# 1_uC.net
KiCad netlist of a schematic drawn in Altium Designer
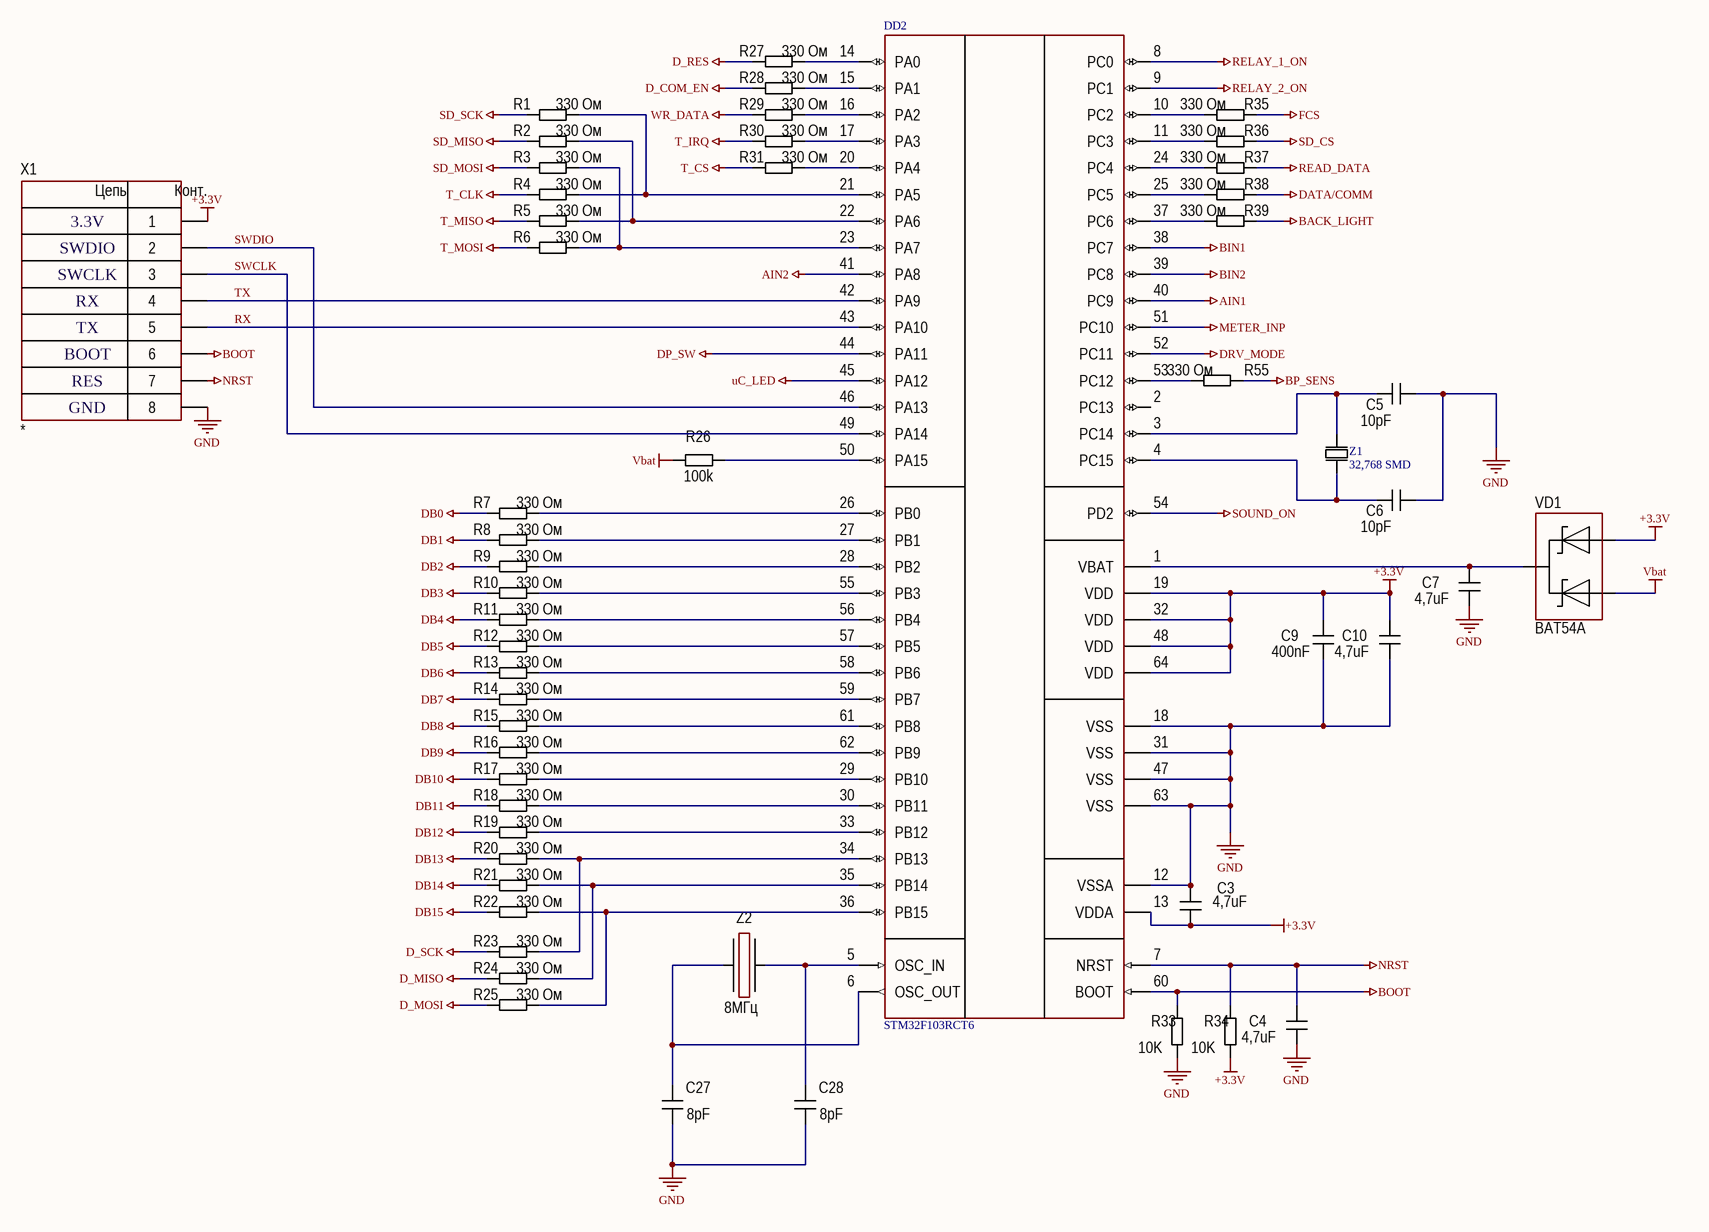
[diagram p0: 1_uC.SchDoc]

(export (version "E")
  (design (tool "Eeschema 10.0.6"))
  (components
    (comp (ref "C3")
      (value "4,7uF")
      (footprint "CH0402C")
      (description "0402")
      (libsource (lib "Condensators") (part "Capacitor"))
    )
    (comp (ref "C4")
      (value "4,7uF")
      (footprint "CH0402C")
      (description "0402")
      (libsource (lib "Condensators") (part "Capacitor"))
    )
    (comp (ref "C5")
      (value "10pF")
      (footprint "CH0402C")
      (description "0402")
      (libsource (lib "Condensators") (part "Capacitor"))
    )
    (comp (ref "C6")
      (value "10pF")
      (footprint "CH0402C")
      (description "0402")
      (libsource (lib "Condensators") (part "Capacitor"))
    )
    (comp (ref "C7")
      (value "4,7uF")
      (footprint "CH0402C")
      (libsource (lib "Condensators") (part "Capacitor"))
    )
    (comp (ref "C9")
      (value "400nF")
      (footprint "CH0402C")
      (description "0402")
      (libsource (lib "Condensators") (part "Capacitor"))
    )
    (comp (ref "C10")
      (value "4,7uF")
      (footprint "CH0402C")
      (description "0402")
      (libsource (lib "Condensators") (part "Capacitor"))
    )
    (comp (ref "C27")
      (value "8pF")
      (footprint "CH0402C")
      (description "0402")
      (libsource (lib "Condensators") (part "Capacitor"))
    )
    (comp (ref "C28")
      (value "8pF")
      (footprint "CH0402C")
      (description "0402")
      (libsource (lib "Condensators") (part "Capacitor"))
    )
    (comp (ref "DD2")
      (value "STM32F103RCT6")
      (footprint "64-LQFP")
      (description "Cortex-M3 (64-LQFP)")
      (libsource (lib "MicroIC") (part "STM32F103RCT6"))
    )
    (comp (ref "R1")
      (value "330 Ом")
      (footprint "CH0603R")
      (description "0603")
      (libsource (lib "Resistors") (part "Resistor"))
    )
    (comp (ref "R2")
      (value "330 Ом")
      (footprint "CH0603R")
      (description "0603")
      (libsource (lib "Resistors") (part "Resistor"))
    )
    (comp (ref "R3")
      (value "330 Ом")
      (footprint "CH0603R")
      (description "0603")
      (libsource (lib "Resistors") (part "Resistor"))
    )
    (comp (ref "R4")
      (value "330 Ом")
      (footprint "CH0603R")
      (description "0603")
      (libsource (lib "Resistors") (part "Resistor"))
    )
    (comp (ref "R5")
      (value "330 Ом")
      (footprint "CH0603R")
      (description "0603")
      (libsource (lib "Resistors") (part "Resistor"))
    )
    (comp (ref "R6")
      (value "330 Ом")
      (footprint "CH0603R")
      (description "0603")
      (libsource (lib "Resistors") (part "Resistor"))
    )
    (comp (ref "R7")
      (value "330 Ом")
      (footprint "CH0603R")
      (description "0603")
      (libsource (lib "Resistors") (part "Resistor"))
    )
    (comp (ref "R8")
      (value "330 Ом")
      (footprint "CH0603R")
      (description "0603")
      (libsource (lib "Resistors") (part "Resistor"))
    )
    (comp (ref "R9")
      (value "330 Ом")
      (footprint "CH0603R")
      (description "0603")
      (libsource (lib "Resistors") (part "Resistor"))
    )
    (comp (ref "R10")
      (value "330 Ом")
      (footprint "CH0603R")
      (description "0603")
      (libsource (lib "Resistors") (part "Resistor"))
    )
    (comp (ref "R11")
      (value "330 Ом")
      (footprint "CH0603R")
      (description "0603")
      (libsource (lib "Resistors") (part "Resistor"))
    )
    (comp (ref "R12")
      (value "330 Ом")
      (footprint "CH0603R")
      (description "0603")
      (libsource (lib "Resistors") (part "Resistor"))
    )
    (comp (ref "R13")
      (value "330 Ом")
      (footprint "CH0603R")
      (description "0603")
      (libsource (lib "Resistors") (part "Resistor"))
    )
    (comp (ref "R14")
      (value "330 Ом")
      (footprint "CH0603R")
      (description "0603")
      (libsource (lib "Resistors") (part "Resistor"))
    )
    (comp (ref "R15")
      (value "330 Ом")
      (footprint "CH0603R")
      (description "0603")
      (libsource (lib "Resistors") (part "Resistor"))
    )
    (comp (ref "R16")
      (value "330 Ом")
      (footprint "CH0603R")
      (description "0603")
      (libsource (lib "Resistors") (part "Resistor"))
    )
    (comp (ref "R17")
      (value "330 Ом")
      (footprint "CH0603R")
      (description "0603")
      (libsource (lib "Resistors") (part "Resistor"))
    )
    (comp (ref "R18")
      (value "330 Ом")
      (footprint "CH0603R")
      (description "0603")
      (libsource (lib "Resistors") (part "Resistor"))
    )
    (comp (ref "R19")
      (value "330 Ом")
      (footprint "CH0603R")
      (description "0603")
      (libsource (lib "Resistors") (part "Resistor"))
    )
    (comp (ref "R20")
      (value "330 Ом")
      (footprint "CH0603R")
      (description "0603")
      (libsource (lib "Resistors") (part "Resistor"))
    )
    (comp (ref "R21")
      (value "330 Ом")
      (footprint "CH0603R")
      (description "0603")
      (libsource (lib "Resistors") (part "Resistor"))
    )
    (comp (ref "R22")
      (value "330 Ом")
      (footprint "CH0603R")
      (description "0603")
      (libsource (lib "Resistors") (part "Resistor"))
    )
    (comp (ref "R23")
      (value "330 Ом")
      (footprint "CH0603R")
      (description "0603")
      (libsource (lib "Resistors") (part "Resistor"))
    )
    (comp (ref "R24")
      (value "330 Ом")
      (footprint "CH0603R")
      (description "0603")
      (libsource (lib "Resistors") (part "Resistor"))
    )
    (comp (ref "R25")
      (value "330 Ом")
      (footprint "CH0603R")
      (description "0603")
      (libsource (lib "Resistors") (part "Resistor"))
    )
    (comp (ref "R26")
      (value "100k")
      (footprint "CH0603R")
      (description "0603")
      (libsource (lib "Resistors") (part "Resistor"))
    )
    (comp (ref "R27")
      (value "330 Ом")
      (footprint "CH0603R")
      (description "0603")
      (libsource (lib "Resistors") (part "Resistor"))
    )
    (comp (ref "R28")
      (value "330 Ом")
      (footprint "CH0603R")
      (description "0603")
      (libsource (lib "Resistors") (part "Resistor"))
    )
    (comp (ref "R29")
      (value "330 Ом")
      (footprint "CH0603R")
      (description "0603")
      (libsource (lib "Resistors") (part "Resistor"))
    )
    (comp (ref "R30")
      (value "330 Ом")
      (footprint "CH0603R")
      (description "0603")
      (libsource (lib "Resistors") (part "Resistor"))
    )
    (comp (ref "R31")
      (value "330 Ом")
      (footprint "CH0603R")
      (description "0603")
      (libsource (lib "Resistors") (part "Resistor"))
    )
    (comp (ref "R33")
      (value "10K")
      (footprint "CH0805R")
      (description "0805")
      (libsource (lib "Resistors") (part "Resistor"))
    )
    (comp (ref "R34")
      (value "10K")
      (footprint "CH0805R")
      (description "0805")
      (libsource (lib "Resistors") (part "Resistor"))
    )
    (comp (ref "R35")
      (value "330 Ом")
      (footprint "CH0603R")
      (description "0603")
      (libsource (lib "Resistors") (part "Resistor"))
    )
    (comp (ref "R36")
      (value "330 Ом")
      (footprint "CH0603R")
      (description "0603")
      (libsource (lib "Resistors") (part "Resistor"))
    )
    (comp (ref "R37")
      (value "330 Ом")
      (footprint "CH0603R")
      (description "0603")
      (libsource (lib "Resistors") (part "Resistor"))
    )
    (comp (ref "R38")
      (value "330 Ом")
      (footprint "CH0603R")
      (description "0603")
      (libsource (lib "Resistors") (part "Resistor"))
    )
    (comp (ref "R39")
      (value "330 Ом")
      (footprint "CH0603R")
      (description "0603")
      (libsource (lib "Resistors") (part "Resistor"))
    )
    (comp (ref "R55")
      (value "330 Ом")
      (footprint "CH0603R")
      (description "0603")
      (libsource (lib "Resistors") (part "Resistor"))
    )
    (comp (ref "VD1")
      (value "BAT54A")
      (footprint "SOT23_123")
      (description "SOT-23")
      (libsource (lib "Diods") (part "Diod Schottky Array v.1"))
    )
    (comp (ref "X1")
      (value "*")
      (footprint "CON: PLS-8")
      (description "Pin header 8")
      (libsource (lib "Connectors") (part "8-Connector"))
    )
    (comp (ref "Z1")
      (value "32,768 SMD")
      (footprint "SMD 32.768KHz")
      (description "32,768 kHz SMD 8mm x 3.8mm 12,5pF")
      (libsource (lib "Melochi") (part "Kvarc_32,768"))
    )
    (comp (ref "Z2")
      (value "8МГц")
      (footprint "OSC: ABM3")
      (description "NX5032GA-8MHz")
      (libsource (lib "Melochi") (part "Oscillator"))
    )
  )
  (nets
    (net (code "1") (name "+3.3V") (class "Default")
      (node (ref "C10") (pin "2") (pinfunction "2_2") (pintype "passive"))
      (node (ref "C3") (pin "1") (pinfunction "1_1") (pintype "passive"))
      (node (ref "C9") (pin "1") (pinfunction "1_1") (pintype "passive"))
      (node (ref "DD2") (pin "13") (pinfunction "VDDA_13") (pintype "power_in"))
      (node (ref "DD2") (pin "19") (pinfunction "VDD_19") (pintype "power_in"))
      (node (ref "DD2") (pin "32") (pinfunction "VDD_32") (pintype "power_in"))
      (node (ref "DD2") (pin "48") (pinfunction "VDD_48") (pintype "power_in"))
      (node (ref "DD2") (pin "64") (pinfunction "VDD_64") (pintype "power_in"))
      (node (ref "R34") (pin "1") (pinfunction "1_1") (pintype "passive"))
      (node (ref "VD1") (pin "1") (pinfunction "1_1") (pintype "passive"))
      (node (ref "X1") (pin "1") (pinfunction "1_1") (pintype "passive"))
    )
    (net (code "2") (name "/RX") (class "Default")
      (node (ref "DD2") (pin "43") (pinfunction "PA10_43") (pintype "bidirectional"))
      (node (ref "X1") (pin "5") (pinfunction "5_5") (pintype "power_in"))
    )
    (net (code "3") (name "/SWCLK") (class "Default")
      (node (ref "DD2") (pin "49") (pinfunction "PA14_49") (pintype "bidirectional"))
      (node (ref "X1") (pin "3") (pinfunction "3_3") (pintype "power_in"))
    )
    (net (code "4") (name "/SWDIO") (class "Default")
      (node (ref "DD2") (pin "46") (pinfunction "PA13_46") (pintype "bidirectional"))
      (node (ref "X1") (pin "2") (pinfunction "2_2") (pintype "passive"))
    )
    (net (code "5") (name "/TX") (class "Default")
      (node (ref "DD2") (pin "42") (pinfunction "PA9_42") (pintype "bidirectional"))
      (node (ref "X1") (pin "4") (pinfunction "4_4") (pintype "power_in"))
    )
    (net (code "6") (name "AIN1") (class "Default")
      (node (ref "DD2") (pin "40") (pinfunction "PC9_40") (pintype "bidirectional"))
    )
    (net (code "7") (name "AIN2") (class "Default")
      (node (ref "DD2") (pin "41") (pinfunction "PA8_41") (pintype "bidirectional"))
    )
    (net (code "8") (name "BACK_LIGHT") (class "Default")
      (node (ref "R39") (pin "1") (pinfunction "1_1") (pintype "passive"))
    )
    (net (code "9") (name "BIN1") (class "Default")
      (node (ref "DD2") (pin "38") (pinfunction "PC7_38") (pintype "bidirectional"))
    )
    (net (code "10") (name "BIN2") (class "Default")
      (node (ref "DD2") (pin "39") (pinfunction "PC8_39") (pintype "bidirectional"))
    )
    (net (code "11") (name "BOOT") (class "Default")
      (node (ref "DD2") (pin "60") (pinfunction "BOOT_60") (pintype "input"))
      (node (ref "R33") (pin "2") (pinfunction "2_2") (pintype "passive"))
      (node (ref "X1") (pin "6") (pinfunction "6_6") (pintype "power_in"))
    )
    (net (code "12") (name "BP_SENS") (class "Default")
      (node (ref "R55") (pin "1") (pinfunction "1_1") (pintype "passive"))
    )
    (net (code "13") (name "DATA{slash}COMM") (class "Default")
      (node (ref "R38") (pin "1") (pinfunction "1_1") (pintype "passive"))
    )
    (net (code "14") (name "DB0") (class "Default")
      (node (ref "R7") (pin "1") (pinfunction "1_1") (pintype "passive"))
    )
    (net (code "15") (name "DB1") (class "Default")
      (node (ref "R8") (pin "1") (pinfunction "1_1") (pintype "passive"))
    )
    (net (code "16") (name "DB2") (class "Default")
      (node (ref "R9") (pin "1") (pinfunction "1_1") (pintype "passive"))
    )
    (net (code "17") (name "DB3") (class "Default")
      (node (ref "R10") (pin "1") (pinfunction "1_1") (pintype "passive"))
    )
    (net (code "18") (name "DB4") (class "Default")
      (node (ref "R11") (pin "1") (pinfunction "1_1") (pintype "passive"))
    )
    (net (code "19") (name "DB5") (class "Default")
      (node (ref "R12") (pin "1") (pinfunction "1_1") (pintype "passive"))
    )
    (net (code "20") (name "DB6") (class "Default")
      (node (ref "R13") (pin "1") (pinfunction "1_1") (pintype "passive"))
    )
    (net (code "21") (name "DB7") (class "Default")
      (node (ref "R14") (pin "1") (pinfunction "1_1") (pintype "passive"))
    )
    (net (code "22") (name "DB8") (class "Default")
      (node (ref "R15") (pin "1") (pinfunction "1_1") (pintype "passive"))
    )
    (net (code "23") (name "DB9") (class "Default")
      (node (ref "R16") (pin "1") (pinfunction "1_1") (pintype "passive"))
    )
    (net (code "24") (name "DB10") (class "Default")
      (node (ref "R17") (pin "1") (pinfunction "1_1") (pintype "passive"))
    )
    (net (code "25") (name "DB11") (class "Default")
      (node (ref "R18") (pin "1") (pinfunction "1_1") (pintype "passive"))
    )
    (net (code "26") (name "DB12") (class "Default")
      (node (ref "R19") (pin "1") (pinfunction "1_1") (pintype "passive"))
    )
    (net (code "27") (name "DB13") (class "Default")
      (node (ref "R20") (pin "1") (pinfunction "1_1") (pintype "passive"))
    )
    (net (code "28") (name "DB14") (class "Default")
      (node (ref "R21") (pin "1") (pinfunction "1_1") (pintype "passive"))
    )
    (net (code "29") (name "DB15") (class "Default")
      (node (ref "R22") (pin "1") (pinfunction "1_1") (pintype "passive"))
    )
    (net (code "30") (name "DP_SW") (class "Default")
      (node (ref "DD2") (pin "44") (pinfunction "PA11_44") (pintype "bidirectional"))
    )
    (net (code "31") (name "DRV_MODE") (class "Default")
      (node (ref "DD2") (pin "52") (pinfunction "PC11_52") (pintype "bidirectional"))
    )
    (net (code "32") (name "D_COM_EN") (class "Default")
      (node (ref "R28") (pin "1") (pinfunction "1_1") (pintype "passive"))
    )
    (net (code "33") (name "D_MISO") (class "Default")
      (node (ref "R24") (pin "1") (pinfunction "1_1") (pintype "passive"))
    )
    (net (code "34") (name "D_MOSI") (class "Default")
      (node (ref "R25") (pin "1") (pinfunction "1_1") (pintype "passive"))
    )
    (net (code "35") (name "D_RES") (class "Default")
      (node (ref "R27") (pin "1") (pinfunction "1_1") (pintype "passive"))
    )
    (net (code "36") (name "D_SCK") (class "Default")
      (node (ref "R23") (pin "1") (pinfunction "1_1") (pintype "passive"))
    )
    (net (code "37") (name "FCS") (class "Default")
      (node (ref "R35") (pin "1") (pinfunction "1_1") (pintype "passive"))
    )
    (net (code "38") (name "GND") (class "Default")
      (node (ref "C10") (pin "1") (pinfunction "1_1") (pintype "passive"))
      (node (ref "C27") (pin "1") (pinfunction "1_1") (pintype "passive"))
      (node (ref "C28") (pin "1") (pinfunction "1_1") (pintype "passive"))
      (node (ref "C3") (pin "2") (pinfunction "2_2") (pintype "passive"))
      (node (ref "C4") (pin "1") (pinfunction "1_1") (pintype "passive"))
      (node (ref "C5") (pin "2") (pinfunction "2_2") (pintype "passive"))
      (node (ref "C6") (pin "1") (pinfunction "1_1") (pintype "passive"))
      (node (ref "C7") (pin "1") (pinfunction "1_1") (pintype "passive"))
      (node (ref "C9") (pin "2") (pinfunction "2_2") (pintype "passive"))
      (node (ref "DD2") (pin "12") (pinfunction "VSSA_12") (pintype "power_in"))
      (node (ref "DD2") (pin "18") (pinfunction "VSS_18") (pintype "power_in"))
      (node (ref "DD2") (pin "31") (pinfunction "VSS_31") (pintype "power_in"))
      (node (ref "DD2") (pin "47") (pinfunction "VSS_47") (pintype "power_in"))
      (node (ref "DD2") (pin "63") (pinfunction "VSS_63") (pintype "power_in"))
      (node (ref "R33") (pin "1") (pinfunction "1_1") (pintype "passive"))
      (node (ref "X1") (pin "8") (pinfunction "8_8") (pintype "power_in"))
    )
    (net (code "39") (name "METER_INP") (class "Default")
      (node (ref "DD2") (pin "51") (pinfunction "PC10_51") (pintype "bidirectional"))
    )
    (net (code "40") (name "NRST") (class "Default")
      (node (ref "C4") (pin "2") (pinfunction "2_2") (pintype "passive"))
      (node (ref "DD2") (pin "7") (pinfunction "NRST_7") (pintype "input"))
      (node (ref "R34") (pin "2") (pinfunction "2_2") (pintype "passive"))
      (node (ref "X1") (pin "7") (pinfunction "7_7") (pintype "power_in"))
    )
    (net (code "41") (name "Net-(DD2-OSC_IN)") (class "Default")
      (node (ref "C28") (pin "2") (pinfunction "2_2") (pintype "passive"))
      (node (ref "DD2") (pin "5") (pinfunction "OSC_IN_5") (pintype "input"))
      (node (ref "Z2") (pin "3") (pinfunction "3_3") (pintype "passive"))
    )
    (net (code "42") (name "Net-(DD2-OSC_OUT)") (class "Default")
      (node (ref "C27") (pin "2") (pinfunction "2_2") (pintype "passive"))
      (node (ref "DD2") (pin "6") (pinfunction "OSC_OUT_6") (pintype "output"))
      (node (ref "Z2") (pin "1") (pinfunction "1_1") (pintype "passive"))
    )
    (net (code "43") (name "Net-(DD2-PA0)") (class "Default")
      (node (ref "DD2") (pin "14") (pinfunction "PA0_14") (pintype "bidirectional"))
      (node (ref "R27") (pin "2") (pinfunction "2_2") (pintype "passive"))
    )
    (net (code "44") (name "Net-(DD2-PA1)") (class "Default")
      (node (ref "DD2") (pin "15") (pinfunction "PA1_15") (pintype "bidirectional"))
      (node (ref "R28") (pin "2") (pinfunction "2_2") (pintype "passive"))
    )
    (net (code "45") (name "Net-(DD2-PA2)") (class "Default")
      (node (ref "DD2") (pin "16") (pinfunction "PA2_16") (pintype "bidirectional"))
      (node (ref "R29") (pin "2") (pinfunction "2_2") (pintype "passive"))
    )
    (net (code "46") (name "Net-(DD2-PA3)") (class "Default")
      (node (ref "DD2") (pin "17") (pinfunction "PA3_17") (pintype "bidirectional"))
      (node (ref "R30") (pin "2") (pinfunction "2_2") (pintype "passive"))
    )
    (net (code "47") (name "Net-(DD2-PA4)") (class "Default")
      (node (ref "DD2") (pin "20") (pinfunction "PA4_20") (pintype "bidirectional"))
      (node (ref "R31") (pin "2") (pinfunction "2_2") (pintype "passive"))
    )
    (net (code "48") (name "Net-(DD2-PA5)") (class "Default")
      (node (ref "DD2") (pin "21") (pinfunction "PA5_21") (pintype "bidirectional"))
      (node (ref "R1") (pin "2") (pinfunction "2_2") (pintype "passive"))
      (node (ref "R4") (pin "2") (pinfunction "2_2") (pintype "passive"))
    )
    (net (code "49") (name "Net-(DD2-PA6)") (class "Default")
      (node (ref "DD2") (pin "22") (pinfunction "PA6_22") (pintype "bidirectional"))
      (node (ref "R2") (pin "2") (pinfunction "2_2") (pintype "passive"))
      (node (ref "R5") (pin "2") (pinfunction "2_2") (pintype "passive"))
    )
    (net (code "50") (name "Net-(DD2-PA7)") (class "Default")
      (node (ref "DD2") (pin "23") (pinfunction "PA7_23") (pintype "bidirectional"))
      (node (ref "R3") (pin "2") (pinfunction "2_2") (pintype "passive"))
      (node (ref "R6") (pin "2") (pinfunction "2_2") (pintype "passive"))
    )
    (net (code "51") (name "Net-(DD2-PA15)") (class "Default")
      (node (ref "DD2") (pin "50") (pinfunction "PA15_50") (pintype "bidirectional"))
      (node (ref "R26") (pin "2") (pinfunction "2_2") (pintype "passive"))
    )
    (net (code "52") (name "Net-(DD2-PB0)") (class "Default")
      (node (ref "DD2") (pin "26") (pinfunction "PB0_26") (pintype "bidirectional"))
      (node (ref "R7") (pin "2") (pinfunction "2_2") (pintype "passive"))
    )
    (net (code "53") (name "Net-(DD2-PB1)") (class "Default")
      (node (ref "DD2") (pin "27") (pinfunction "PB1_27") (pintype "bidirectional"))
      (node (ref "R8") (pin "2") (pinfunction "2_2") (pintype "passive"))
    )
    (net (code "54") (name "Net-(DD2-PB2)") (class "Default")
      (node (ref "DD2") (pin "28") (pinfunction "PB2_28") (pintype "bidirectional"))
      (node (ref "R9") (pin "2") (pinfunction "2_2") (pintype "passive"))
    )
    (net (code "55") (name "Net-(DD2-PB3)") (class "Default")
      (node (ref "DD2") (pin "55") (pinfunction "PB3_55") (pintype "bidirectional"))
      (node (ref "R10") (pin "2") (pinfunction "2_2") (pintype "passive"))
    )
    (net (code "56") (name "Net-(DD2-PB4)") (class "Default")
      (node (ref "DD2") (pin "56") (pinfunction "PB4_56") (pintype "bidirectional"))
      (node (ref "R11") (pin "2") (pinfunction "2_2") (pintype "passive"))
    )
    (net (code "57") (name "Net-(DD2-PB5)") (class "Default")
      (node (ref "DD2") (pin "57") (pinfunction "PB5_57") (pintype "bidirectional"))
      (node (ref "R12") (pin "2") (pinfunction "2_2") (pintype "passive"))
    )
    (net (code "58") (name "Net-(DD2-PB6)") (class "Default")
      (node (ref "DD2") (pin "58") (pinfunction "PB6_58") (pintype "bidirectional"))
      (node (ref "R13") (pin "2") (pinfunction "2_2") (pintype "passive"))
    )
    (net (code "59") (name "Net-(DD2-PB7)") (class "Default")
      (node (ref "DD2") (pin "59") (pinfunction "PB7_59") (pintype "bidirectional"))
      (node (ref "R14") (pin "2") (pinfunction "2_2") (pintype "passive"))
    )
    (net (code "60") (name "Net-(DD2-PB8)") (class "Default")
      (node (ref "DD2") (pin "61") (pinfunction "PB8_61") (pintype "bidirectional"))
      (node (ref "R15") (pin "2") (pinfunction "2_2") (pintype "passive"))
    )
    (net (code "61") (name "Net-(DD2-PB9)") (class "Default")
      (node (ref "DD2") (pin "62") (pinfunction "PB9_62") (pintype "bidirectional"))
      (node (ref "R16") (pin "2") (pinfunction "2_2") (pintype "passive"))
    )
    (net (code "62") (name "Net-(DD2-PB10)") (class "Default")
      (node (ref "DD2") (pin "29") (pinfunction "PB10_29") (pintype "bidirectional"))
      (node (ref "R17") (pin "2") (pinfunction "2_2") (pintype "passive"))
    )
    (net (code "63") (name "Net-(DD2-PB11)") (class "Default")
      (node (ref "DD2") (pin "30") (pinfunction "PB11_30") (pintype "bidirectional"))
      (node (ref "R18") (pin "2") (pinfunction "2_2") (pintype "passive"))
    )
    (net (code "64") (name "Net-(DD2-PB12)") (class "Default")
      (node (ref "DD2") (pin "33") (pinfunction "PB12_33") (pintype "bidirectional"))
      (node (ref "R19") (pin "2") (pinfunction "2_2") (pintype "passive"))
    )
    (net (code "65") (name "Net-(DD2-PB13)") (class "Default")
      (node (ref "DD2") (pin "34") (pinfunction "PB13_34") (pintype "bidirectional"))
      (node (ref "R20") (pin "2") (pinfunction "2_2") (pintype "passive"))
      (node (ref "R23") (pin "2") (pinfunction "2_2") (pintype "passive"))
    )
    (net (code "66") (name "Net-(DD2-PB14)") (class "Default")
      (node (ref "DD2") (pin "35") (pinfunction "PB14_35") (pintype "bidirectional"))
      (node (ref "R21") (pin "2") (pinfunction "2_2") (pintype "passive"))
      (node (ref "R24") (pin "2") (pinfunction "2_2") (pintype "passive"))
    )
    (net (code "67") (name "Net-(DD2-PB15)") (class "Default")
      (node (ref "DD2") (pin "36") (pinfunction "PB15_36") (pintype "bidirectional"))
      (node (ref "R22") (pin "2") (pinfunction "2_2") (pintype "passive"))
      (node (ref "R25") (pin "2") (pinfunction "2_2") (pintype "passive"))
    )
    (net (code "68") (name "Net-(DD2-PC2)") (class "Default")
      (node (ref "DD2") (pin "10") (pinfunction "PC2_10") (pintype "bidirectional"))
      (node (ref "R35") (pin "2") (pinfunction "2_2") (pintype "passive"))
    )
    (net (code "69") (name "Net-(DD2-PC3)") (class "Default")
      (node (ref "DD2") (pin "11") (pinfunction "PC3_11") (pintype "bidirectional"))
      (node (ref "R36") (pin "2") (pinfunction "2_2") (pintype "passive"))
    )
    (net (code "70") (name "Net-(DD2-PC4)") (class "Default")
      (node (ref "DD2") (pin "24") (pinfunction "PC4_24") (pintype "bidirectional"))
      (node (ref "R37") (pin "2") (pinfunction "2_2") (pintype "passive"))
    )
    (net (code "71") (name "Net-(DD2-PC5)") (class "Default")
      (node (ref "DD2") (pin "25") (pinfunction "PC5_25") (pintype "bidirectional"))
      (node (ref "R38") (pin "2") (pinfunction "2_2") (pintype "passive"))
    )
    (net (code "72") (name "Net-(DD2-PC6)") (class "Default")
      (node (ref "DD2") (pin "37") (pinfunction "PC6_37") (pintype "bidirectional"))
      (node (ref "R39") (pin "2") (pinfunction "2_2") (pintype "passive"))
    )
    (net (code "73") (name "Net-(DD2-PC12)") (class "Default")
      (node (ref "DD2") (pin "53") (pinfunction "PC12_53") (pintype "bidirectional"))
      (node (ref "R55") (pin "2") (pinfunction "2_2") (pintype "passive"))
    )
    (net (code "74") (name "Net-(DD2-PC14)") (class "Default")
      (node (ref "C5") (pin "1") (pinfunction "1_1") (pintype "passive"))
      (node (ref "DD2") (pin "3") (pinfunction "PC14_3") (pintype "bidirectional"))
      (node (ref "Z1") (pin "1") (pinfunction "1_1") (pintype "passive"))
    )
    (net (code "75") (name "Net-(DD2-PC15)") (class "Default")
      (node (ref "C6") (pin "2") (pinfunction "2_2") (pintype "passive"))
      (node (ref "DD2") (pin "4") (pinfunction "PC15_4") (pintype "bidirectional"))
      (node (ref "Z1") (pin "2") (pinfunction "2_2") (pintype "passive"))
    )
    (net (code "76") (name "Net-(DD2-VBAT)") (class "Default")
      (node (ref "C7") (pin "2") (pinfunction "2_2") (pintype "passive"))
      (node (ref "DD2") (pin "1") (pinfunction "VBAT_1") (pintype "power_in"))
      (node (ref "VD1") (pin "2") (pinfunction "2_2") (pintype "passive"))
    )
    (net (code "77") (name "READ_DATA") (class "Default")
      (node (ref "R37") (pin "1") (pinfunction "1_1") (pintype "passive"))
    )
    (net (code "78") (name "RELAY_1_ON") (class "Default")
      (node (ref "DD2") (pin "8") (pinfunction "PC0_8") (pintype "bidirectional"))
    )
    (net (code "79") (name "RELAY_2_ON") (class "Default")
      (node (ref "DD2") (pin "9") (pinfunction "PC1_9") (pintype "bidirectional"))
    )
    (net (code "80") (name "SD_CS") (class "Default")
      (node (ref "R36") (pin "1") (pinfunction "1_1") (pintype "passive"))
    )
    (net (code "81") (name "SD_MISO") (class "Default")
      (node (ref "R2") (pin "1") (pinfunction "1_1") (pintype "passive"))
    )
    (net (code "82") (name "SD_MOSI") (class "Default")
      (node (ref "R3") (pin "1") (pinfunction "1_1") (pintype "passive"))
    )
    (net (code "83") (name "SD_SCK") (class "Default")
      (node (ref "R1") (pin "1") (pinfunction "1_1") (pintype "passive"))
    )
    (net (code "84") (name "SOUND_ON") (class "Default")
      (node (ref "DD2") (pin "54") (pinfunction "PD2_54") (pintype "bidirectional"))
    )
    (net (code "85") (name "T_CLK") (class "Default")
      (node (ref "R4") (pin "1") (pinfunction "1_1") (pintype "passive"))
    )
    (net (code "86") (name "T_CS") (class "Default")
      (node (ref "R31") (pin "1") (pinfunction "1_1") (pintype "passive"))
    )
    (net (code "87") (name "T_IRQ") (class "Default")
      (node (ref "R30") (pin "1") (pinfunction "1_1") (pintype "passive"))
    )
    (net (code "88") (name "T_MISO") (class "Default")
      (node (ref "R5") (pin "1") (pinfunction "1_1") (pintype "passive"))
    )
    (net (code "89") (name "T_MOSI") (class "Default")
      (node (ref "R6") (pin "1") (pinfunction "1_1") (pintype "passive"))
    )
    (net (code "90") (name "Vbat") (class "Default")
      (node (ref "R26") (pin "1") (pinfunction "1_1") (pintype "passive"))
      (node (ref "VD1") (pin "3") (pinfunction "3_3") (pintype "passive"))
    )
    (net (code "91") (name "WR_DATA") (class "Default")
      (node (ref "R29") (pin "1") (pinfunction "1_1") (pintype "passive"))
    )
    (net (code "92") (name "uC_LED") (class "Default")
      (node (ref "DD2") (pin "45") (pinfunction "PA12_45") (pintype "bidirectional"))
    )
    (net (code "93") (name "unconnected-(DD2-PC13-Pad2)") (class "Default")
      (node (ref "DD2") (pin "2") (pinfunction "PC13_2") (pintype "bidirectional"))
    )
  )
)
